# Emanuel_textured_walkway_V1.net
KiCad netlist of a schematic drawn in EAGLE
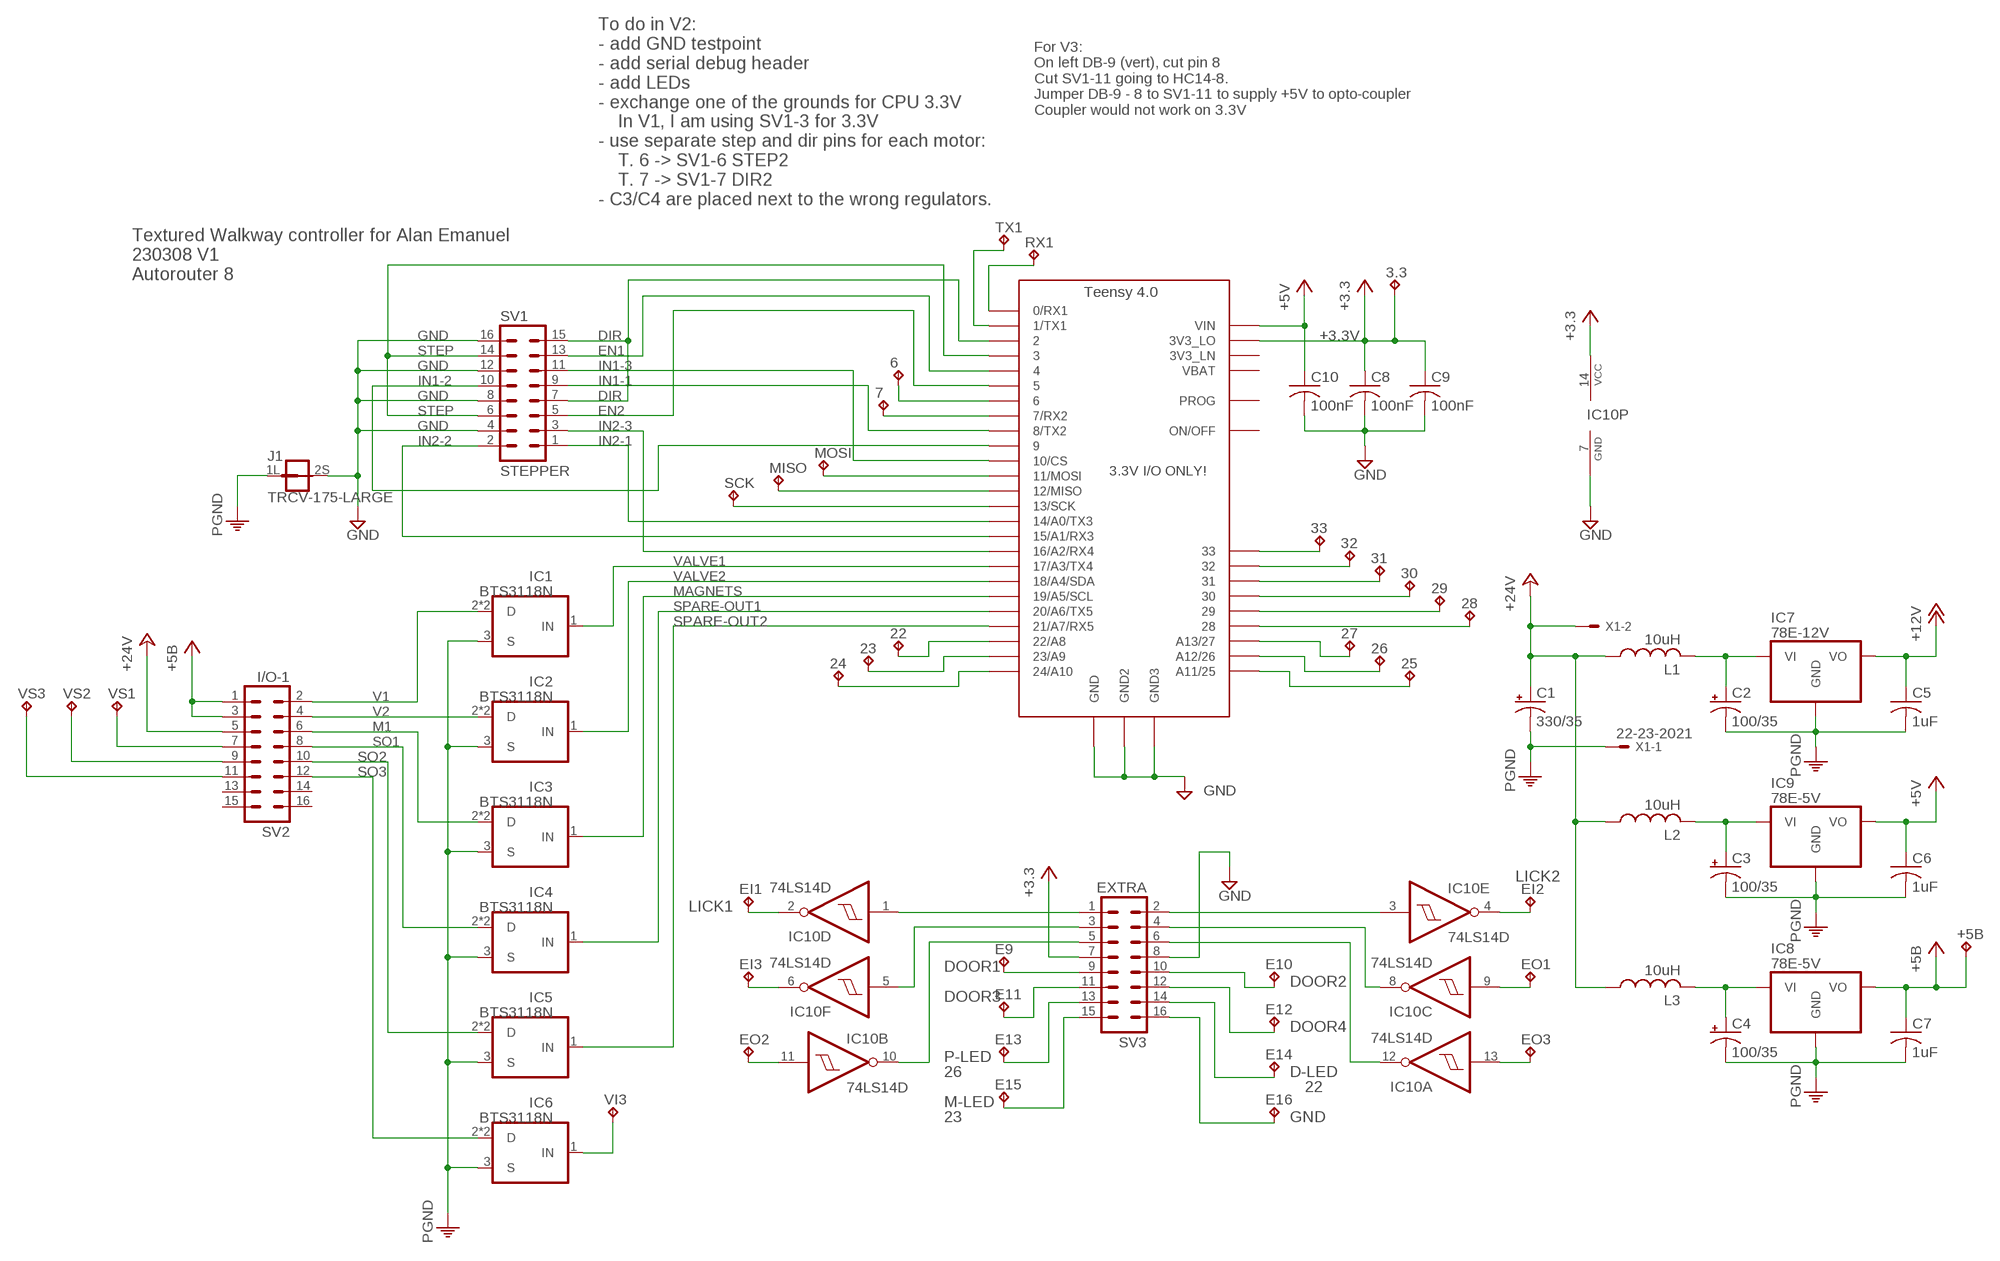
[diagram p0: schematic, sheet 1]

(export (version "E")
  (design (tool "Eeschema 10.0.6"))
  (components
    (comp (ref "+5B")
      (value "TP-040-100")
      (footprint "eagle-import:P1-040-100")
      (libsource (lib "eagle-import") (part "TP-040-100"))
    )
    (comp (ref "3.3")
      (value "3.3")
      (footprint "eagle-import:P1-040-100")
      (libsource (lib "eagle-import") (part "TP-040-100"))
    )
    (comp (ref "6")
      (value "TP-040-100")
      (footprint "eagle-import:P1-040-100")
      (libsource (lib "eagle-import") (part "TP-040-100"))
    )
    (comp (ref "7")
      (value "TP-040-100")
      (footprint "eagle-import:P1-040-100")
      (libsource (lib "eagle-import") (part "TP-040-100"))
    )
    (comp (ref "22")
      (value "TP-040-100")
      (footprint "eagle-import:P1-040-100")
      (libsource (lib "eagle-import") (part "TP-040-100"))
    )
    (comp (ref "23")
      (value "TP-040-100")
      (footprint "eagle-import:P1-040-100")
      (libsource (lib "eagle-import") (part "TP-040-100"))
    )
    (comp (ref "24")
      (value "TP-040-100")
      (footprint "eagle-import:P1-040-100")
      (libsource (lib "eagle-import") (part "TP-040-100"))
    )
    (comp (ref "25")
      (value "TP-040-100")
      (footprint "eagle-import:P1-040-100")
      (libsource (lib "eagle-import") (part "TP-040-100"))
    )
    (comp (ref "26")
      (value "TP-040-100")
      (footprint "eagle-import:P1-040-100")
      (libsource (lib "eagle-import") (part "TP-040-100"))
    )
    (comp (ref "27")
      (value "TP-040-100")
      (footprint "eagle-import:P1-040-100")
      (libsource (lib "eagle-import") (part "TP-040-100"))
    )
    (comp (ref "28")
      (value "TP-040-100")
      (footprint "eagle-import:P1-040-100")
      (libsource (lib "eagle-import") (part "TP-040-100"))
    )
    (comp (ref "29")
      (value "TP-040-100")
      (footprint "eagle-import:P1-040-100")
      (libsource (lib "eagle-import") (part "TP-040-100"))
    )
    (comp (ref "30")
      (value "TP-040-100")
      (footprint "eagle-import:P1-040-100")
      (libsource (lib "eagle-import") (part "TP-040-100"))
    )
    (comp (ref "31")
      (value "TP-040-100")
      (footprint "eagle-import:P1-040-100")
      (libsource (lib "eagle-import") (part "TP-040-100"))
    )
    (comp (ref "32")
      (value "TP-040-100")
      (footprint "eagle-import:P1-040-100")
      (libsource (lib "eagle-import") (part "TP-040-100"))
    )
    (comp (ref "33")
      (value "TP-040-100")
      (footprint "eagle-import:P1-040-100")
      (libsource (lib "eagle-import") (part "TP-040-100"))
    )
    (comp (ref "C1")
      (value "330/35")
      (footprint "eagle-import:140CLH-1010")
      (libsource (lib "eagle-import") (part "CPOL-US140CLH-1010"))
    )
    (comp (ref "C2")
      (value "100/35")
      (footprint "eagle-import:140CLH-0810")
      (libsource (lib "eagle-import") (part "CPOL-US140CLH-0810"))
    )
    (comp (ref "C3")
      (value "100/35")
      (footprint "eagle-import:140CLH-0810")
      (libsource (lib "eagle-import") (part "CPOL-US140CLH-0810"))
    )
    (comp (ref "C4")
      (value "100/35")
      (footprint "eagle-import:140CLH-0810")
      (libsource (lib "eagle-import") (part "CPOL-US140CLH-0810"))
    )
    (comp (ref "C5")
      (value "1uF")
      (footprint "eagle-import:C0805")
      (libsource (lib "eagle-import") (part "C-USC0805"))
    )
    (comp (ref "C6")
      (value "1uF")
      (footprint "eagle-import:C0805")
      (libsource (lib "eagle-import") (part "C-USC0805"))
    )
    (comp (ref "C7")
      (value "1uF")
      (footprint "eagle-import:C0805")
      (libsource (lib "eagle-import") (part "C-USC0805"))
    )
    (comp (ref "C8")
      (value "100nF")
      (footprint "eagle-import:C0805")
      (libsource (lib "eagle-import") (part "C-USC0805"))
    )
    (comp (ref "C9")
      (value "100nF")
      (footprint "eagle-import:C0805")
      (libsource (lib "eagle-import") (part "C-USC0805"))
    )
    (comp (ref "C10")
      (value "100nF")
      (footprint "eagle-import:C0805")
      (libsource (lib "eagle-import") (part "C-USC0805"))
    )
    (comp (ref "E9")
      (value "TP-040-100")
      (footprint "eagle-import:P1-040-100")
      (libsource (lib "eagle-import") (part "TP-040-100"))
    )
    (comp (ref "E10")
      (value "TP-040-100")
      (footprint "eagle-import:P1-040-100")
      (libsource (lib "eagle-import") (part "TP-040-100"))
    )
    (comp (ref "E11")
      (value "TP-040-100")
      (footprint "eagle-import:P1-040-100")
      (libsource (lib "eagle-import") (part "TP-040-100"))
    )
    (comp (ref "E12")
      (value "TP-040-100")
      (footprint "eagle-import:P1-040-100")
      (libsource (lib "eagle-import") (part "TP-040-100"))
    )
    (comp (ref "E13")
      (value "TP-040-100")
      (footprint "eagle-import:P1-040-100")
      (libsource (lib "eagle-import") (part "TP-040-100"))
    )
    (comp (ref "E14")
      (value "TP-040-100")
      (footprint "eagle-import:P1-040-100")
      (libsource (lib "eagle-import") (part "TP-040-100"))
    )
    (comp (ref "E15")
      (value "TP-040-100")
      (footprint "eagle-import:P1-040-100")
      (libsource (lib "eagle-import") (part "TP-040-100"))
    )
    (comp (ref "E16")
      (value "TP-040-100")
      (footprint "eagle-import:P1-040-100")
      (libsource (lib "eagle-import") (part "TP-040-100"))
    )
    (comp (ref "EI1")
      (value "TP-040-100")
      (footprint "eagle-import:P1-040-100")
      (libsource (lib "eagle-import") (part "TP-040-100"))
    )
    (comp (ref "EI2")
      (value "TP-040-100")
      (footprint "eagle-import:P1-040-100")
      (libsource (lib "eagle-import") (part "TP-040-100"))
    )
    (comp (ref "EI3")
      (value "TP-040-100")
      (footprint "eagle-import:P1-040-100")
      (libsource (lib "eagle-import") (part "TP-040-100"))
    )
    (comp (ref "EO1")
      (value "TP-040-100")
      (footprint "eagle-import:P1-040-100")
      (libsource (lib "eagle-import") (part "TP-040-100"))
    )
    (comp (ref "EO2")
      (value "TP-040-100")
      (footprint "eagle-import:P1-040-100")
      (libsource (lib "eagle-import") (part "TP-040-100"))
    )
    (comp (ref "EO3")
      (value "TP-040-100")
      (footprint "eagle-import:P1-040-100")
      (libsource (lib "eagle-import") (part "TP-040-100"))
    )
    (comp (ref "IC1")
      (value "BTS3118N")
      (footprint "eagle-import:SOT223")
      (libsource (lib "eagle-import") (part "BTS3118N"))
    )
    (comp (ref "IC2")
      (value "BTS3118N")
      (footprint "eagle-import:SOT223")
      (libsource (lib "eagle-import") (part "BTS3118N"))
    )
    (comp (ref "IC3")
      (value "BTS3118N")
      (footprint "eagle-import:SOT223")
      (libsource (lib "eagle-import") (part "BTS3118N"))
    )
    (comp (ref "IC4")
      (value "BTS3118N")
      (footprint "eagle-import:SOT223")
      (libsource (lib "eagle-import") (part "BTS3118N"))
    )
    (comp (ref "IC5")
      (value "BTS3118N")
      (footprint "eagle-import:SOT223")
      (libsource (lib "eagle-import") (part "BTS3118N"))
    )
    (comp (ref "IC6")
      (value "BTS3118N")
      (footprint "eagle-import:SOT223")
      (libsource (lib "eagle-import") (part "BTS3118N"))
    )
    (comp (ref "IC7")
      (value "78E-12V")
      (footprint "eagle-import:RECOM-R-78E")
      (libsource (lib "eagle-import") (part "RECOM-R-78E"))
    )
    (comp (ref "IC8")
      (value "78E-5V")
      (footprint "eagle-import:RECOM-R-78E")
      (libsource (lib "eagle-import") (part "RECOM-R-78E"))
    )
    (comp (ref "IC9")
      (value "78E-5V")
      (footprint "eagle-import:RECOM-R-78E")
      (libsource (lib "eagle-import") (part "RECOM-R-78E"))
    )
    (comp (ref "IC10")
      (value "74LS14D")
      (footprint "eagle-import:SO14")
      (libsource (lib "eagle-import") (part "7414DLS"))
    )
    (comp (ref "J1")
      (value "TRCV-175-LARGE")
      (footprint "eagle-import:JUMPER-TRACE-CONVERT-LARGER-PADS-175")
      (libsource (lib "eagle-import") (part "TRCV-175-LARGE"))
    )
    (comp (ref "L1")
      (value "10uH")
      (footprint "eagle-import:L1812")
      (libsource (lib "eagle-import") (part "L-USL1812"))
    )
    (comp (ref "L2")
      (value "10uH")
      (footprint "eagle-import:L1812")
      (libsource (lib "eagle-import") (part "L-USL1812"))
    )
    (comp (ref "L3")
      (value "10uH")
      (footprint "eagle-import:L1812")
      (libsource (lib "eagle-import") (part "L-USL1812"))
    )
    (comp (ref "MISO")
      (value "TP-040-100")
      (footprint "eagle-import:P1-040-100")
      (libsource (lib "eagle-import") (part "TP-040-100"))
    )
    (comp (ref "MOSI")
      (value "TP-040-100")
      (footprint "eagle-import:P1-040-100")
      (libsource (lib "eagle-import") (part "TP-040-100"))
    )
    (comp (ref "RX1")
      (value "TP-040-100")
      (footprint "eagle-import:P1-040-100")
      (libsource (lib "eagle-import") (part "TP-040-100"))
    )
    (comp (ref "SCK")
      (value "TP-040-100")
      (footprint "eagle-import:P1-040-100")
      (libsource (lib "eagle-import") (part "TP-040-100"))
    )
    (comp (ref "SV1")
      (value "STEPPER")
      (footprint "eagle-import:ML16")
      (libsource (lib "eagle-import") (part "ML16"))
    )
    (comp (ref "SV2")
      (value "I/O-1")
      (footprint "eagle-import:ML16")
      (libsource (lib "eagle-import") (part "ML16"))
    )
    (comp (ref "SV3")
      (value "EXTRA")
      (footprint "eagle-import:ML16")
      (libsource (lib "eagle-import") (part "ML16"))
    )
    (comp (ref "TX1")
      (value "TP-040-100")
      (footprint "eagle-import:P1-040-100")
      (libsource (lib "eagle-import") (part "TP-040-100"))
    )
    (comp (ref "U$1")
      (value "TEENSY_4.0_WITH_24-33")
      (footprint "eagle-import:TEENSY_4.0_WITH_24-33")
      (libsource (lib "eagle-import") (part "TEENSY_4.0_WITH_24-33"))
    )
    (comp (ref "VI3")
      (value "TP-040-100")
      (footprint "eagle-import:P1-040-100")
      (libsource (lib "eagle-import") (part "TP-040-100"))
    )
    (comp (ref "VS1")
      (value "TP-040-100")
      (footprint "eagle-import:P1-040-100")
      (libsource (lib "eagle-import") (part "TP-040-100"))
    )
    (comp (ref "VS2")
      (value "TP-040-100")
      (footprint "eagle-import:P1-040-100")
      (libsource (lib "eagle-import") (part "TP-040-100"))
    )
    (comp (ref "VS3")
      (value "TP-040-100")
      (footprint "eagle-import:P1-040-100")
      (libsource (lib "eagle-import") (part "TP-040-100"))
    )
    (comp (ref "X1")
      (value "22-23-2021")
      (footprint "eagle-import:22-23-2021")
      (fields (field (name "MF") "MOLEX"))
      (libsource (lib "eagle-import") (part "22-23-2021"))
    )
  )
  (nets
    (net (code "1") (name "+3.3") (class "Default")
      (node (ref "3.3") (pin "P$1") (pinfunction "TP_P$1") (pintype "passive"))
      (node (ref "C8") (pin "1") (pinfunction "1_1") (pintype "passive"))
      (node (ref "C9") (pin "1") (pinfunction "1_1") (pintype "passive"))
      (node (ref "IC10") (pin "14") (pinfunction "VCC_14") (pintype "power_in"))
      (node (ref "SV3") (pin "7") (pinfunction "7_7") (pintype "passive"))
      (node (ref "U$1") (pin "3V3_LO") (pinfunction "3V3_LO_3V3_LO") (pintype "bidirectional"))
    )
    (net (code "2") (name "+5B") (class "Default")
      (node (ref "+5B") (pin "P$1") (pinfunction "TP_P$1") (pintype "passive"))
      (node (ref "C7") (pin "1") (pinfunction "1_1") (pintype "passive"))
      (node (ref "IC8") (pin "3") (pinfunction "VO_3") (pintype "passive"))
      (node (ref "SV2") (pin "1") (pinfunction "1_1") (pintype "passive"))
      (node (ref "SV2") (pin "3") (pinfunction "3_3") (pintype "passive"))
    )
    (net (code "3") (name "+5V") (class "Default")
      (node (ref "C10") (pin "1") (pinfunction "1_1") (pintype "passive"))
      (node (ref "C6") (pin "1") (pinfunction "1_1") (pintype "passive"))
      (node (ref "IC9") (pin "3") (pinfunction "VO_3") (pintype "passive"))
      (node (ref "U$1") (pin "VIN") (pinfunction "VIN_VIN") (pintype "bidirectional"))
    )
    (net (code "4") (name "+12V") (class "Default")
      (node (ref "C5") (pin "1") (pinfunction "1_1") (pintype "passive"))
      (node (ref "IC7") (pin "3") (pinfunction "VO_3") (pintype "passive"))
    )
    (net (code "5") (name "+24V") (class "Default")
      (node (ref "C1") (pin "+") (pinfunction "+_+") (pintype "passive"))
      (node (ref "L1") (pin "1") (pinfunction "1_1") (pintype "passive"))
      (node (ref "L2") (pin "1") (pinfunction "1_1") (pintype "passive"))
      (node (ref "L3") (pin "1") (pinfunction "1_1") (pintype "passive"))
      (node (ref "SV2") (pin "5") (pinfunction "5_5") (pintype "passive"))
      (node (ref "X1") (pin "2") (pinfunction "S_2") (pintype "passive"))
    )
    (net (code "6") (name "/DIR") (class "Default")
      (node (ref "SV1") (pin "15") (pinfunction "15_15") (pintype "passive"))
      (node (ref "SV1") (pin "7") (pinfunction "7_7") (pintype "passive"))
      (node (ref "U$1") (pin "2") (pinfunction "2_2") (pintype "bidirectional"))
    )
    (net (code "7") (name "/EN1") (class "Default")
      (node (ref "SV1") (pin "13") (pinfunction "13_13") (pintype "passive"))
      (node (ref "U$1") (pin "4") (pinfunction "4_4") (pintype "bidirectional"))
    )
    (net (code "8") (name "/EN2") (class "Default")
      (node (ref "SV1") (pin "5") (pinfunction "5_5") (pintype "passive"))
      (node (ref "U$1") (pin "5") (pinfunction "5_5") (pintype "bidirectional"))
    )
    (net (code "9") (name "/IN1-1") (class "Default")
      (node (ref "SV1") (pin "9") (pinfunction "9_9") (pintype "passive"))
      (node (ref "U$1") (pin "8") (pinfunction "8/TX2_8") (pintype "bidirectional"))
    )
    (net (code "10") (name "/IN1-2") (class "Default")
      (node (ref "SV1") (pin "10") (pinfunction "10_10") (pintype "passive"))
      (node (ref "U$1") (pin "9") (pinfunction "9_9") (pintype "bidirectional"))
    )
    (net (code "11") (name "/IN1-3") (class "Default")
      (node (ref "SV1") (pin "11") (pinfunction "11_11") (pintype "passive"))
      (node (ref "U$1") (pin "10/CS") (pinfunction "10/CS_10/CS") (pintype "bidirectional"))
    )
    (net (code "12") (name "/IN2-1") (class "Default")
      (node (ref "SV1") (pin "1") (pinfunction "1_1") (pintype "passive"))
      (node (ref "U$1") (pin "14/A0") (pinfunction "14/A0/TX3_14/A0") (pintype "bidirectional"))
    )
    (net (code "13") (name "/IN2-2") (class "Default")
      (node (ref "SV1") (pin "2") (pinfunction "2_2") (pintype "passive"))
      (node (ref "U$1") (pin "15/A1") (pinfunction "15/A1/RX3_15/A1") (pintype "bidirectional"))
    )
    (net (code "14") (name "/IN2-3") (class "Default")
      (node (ref "SV1") (pin "3") (pinfunction "3_3") (pintype "passive"))
      (node (ref "U$1") (pin "16/A2") (pinfunction "16/A2/RX4_16/A2") (pintype "bidirectional"))
    )
    (net (code "15") (name "/M1") (class "Default")
      (node (ref "IC3") (pin "2") (pinfunction "D_2") (pintype "passive"))
      (node (ref "IC3") (pin "4") (pinfunction "D_4") (pintype "passive"))
      (node (ref "SV2") (pin "6") (pinfunction "6_6") (pintype "passive"))
    )
    (net (code "16") (name "/MAGNETS") (class "Default")
      (node (ref "IC3") (pin "1") (pinfunction "IN_1") (pintype "input"))
      (node (ref "U$1") (pin "19/A5/SCL") (pinfunction "19/A5/SCL_19/A5/SCL") (pintype "bidirectional"))
    )
    (net (code "17") (name "/SO1") (class "Default")
      (node (ref "IC4") (pin "2") (pinfunction "D_2") (pintype "passive"))
      (node (ref "IC4") (pin "4") (pinfunction "D_4") (pintype "passive"))
      (node (ref "SV2") (pin "8") (pinfunction "8_8") (pintype "passive"))
    )
    (net (code "18") (name "/SO2") (class "Default")
      (node (ref "IC5") (pin "2") (pinfunction "D_2") (pintype "passive"))
      (node (ref "IC5") (pin "4") (pinfunction "D_4") (pintype "passive"))
      (node (ref "SV2") (pin "10") (pinfunction "10_10") (pintype "passive"))
    )
    (net (code "19") (name "/SO3") (class "Default")
      (node (ref "IC6") (pin "2") (pinfunction "D_2") (pintype "passive"))
      (node (ref "IC6") (pin "4") (pinfunction "D_4") (pintype "passive"))
      (node (ref "SV2") (pin "12") (pinfunction "12_12") (pintype "passive"))
    )
    (net (code "20") (name "/SPARE-OUT1") (class "Default")
      (node (ref "IC4") (pin "1") (pinfunction "IN_1") (pintype "input"))
      (node (ref "U$1") (pin "20/A6") (pinfunction "20/A6/TX5_20/A6") (pintype "bidirectional"))
    )
    (net (code "21") (name "/SPARE-OUT2") (class "Default")
      (node (ref "IC5") (pin "1") (pinfunction "IN_1") (pintype "input"))
      (node (ref "U$1") (pin "21/A7") (pinfunction "21/A7/RX5_21/A7") (pintype "bidirectional"))
    )
    (net (code "22") (name "/STEP") (class "Default")
      (node (ref "SV1") (pin "14") (pinfunction "14_14") (pintype "passive"))
      (node (ref "SV1") (pin "6") (pinfunction "6_6") (pintype "passive"))
      (node (ref "U$1") (pin "3") (pinfunction "3_3") (pintype "bidirectional"))
    )
    (net (code "23") (name "/V1") (class "Default")
      (node (ref "IC1") (pin "2") (pinfunction "D_2") (pintype "passive"))
      (node (ref "IC1") (pin "4") (pinfunction "D_4") (pintype "passive"))
      (node (ref "SV2") (pin "2") (pinfunction "2_2") (pintype "passive"))
    )
    (net (code "24") (name "/V2") (class "Default")
      (node (ref "IC2") (pin "2") (pinfunction "D_2") (pintype "passive"))
      (node (ref "IC2") (pin "4") (pinfunction "D_4") (pintype "passive"))
      (node (ref "SV2") (pin "4") (pinfunction "4_4") (pintype "passive"))
    )
    (net (code "25") (name "/VALVE1") (class "Default")
      (node (ref "IC1") (pin "1") (pinfunction "IN_1") (pintype "input"))
      (node (ref "U$1") (pin "17/A3") (pinfunction "17/A3/TX4_17/A3") (pintype "bidirectional"))
    )
    (net (code "26") (name "/VALVE2") (class "Default")
      (node (ref "IC2") (pin "1") (pinfunction "IN_1") (pintype "input"))
      (node (ref "U$1") (pin "18/A4/SDA") (pinfunction "18/A4/SDA_18/A4/SDA") (pintype "bidirectional"))
    )
    (net (code "27") (name "GND") (class "Default")
      (node (ref "C10") (pin "2") (pinfunction "2_2") (pintype "passive"))
      (node (ref "C8") (pin "2") (pinfunction "2_2") (pintype "passive"))
      (node (ref "C9") (pin "2") (pinfunction "2_2") (pintype "passive"))
      (node (ref "IC10") (pin "7") (pinfunction "GND_7") (pintype "power_in"))
      (node (ref "J1") (pin "2S") (pinfunction "2_2S") (pintype "passive"))
      (node (ref "SV1") (pin "12") (pinfunction "12_12") (pintype "passive"))
      (node (ref "SV1") (pin "16") (pinfunction "16_16") (pintype "passive"))
      (node (ref "SV1") (pin "4") (pinfunction "4_4") (pintype "passive"))
      (node (ref "SV1") (pin "8") (pinfunction "8_8") (pintype "passive"))
      (node (ref "SV3") (pin "8") (pinfunction "8_8") (pintype "passive"))
      (node (ref "U$1") (pin "GND") (pinfunction "GND_GND") (pintype "bidirectional"))
      (node (ref "U$1") (pin "GND2") (pinfunction "GND2_GND2") (pintype "bidirectional"))
      (node (ref "U$1") (pin "GND3") (pinfunction "GND3_GND3") (pintype "bidirectional"))
    )
    (net (code "28") (name "Net-(6-TP)") (class "Default")
      (node (ref "6") (pin "P$1") (pinfunction "TP_P$1") (pintype "passive"))
      (node (ref "U$1") (pin "6") (pinfunction "6_6") (pintype "bidirectional"))
    )
    (net (code "29") (name "Net-(7-TP)") (class "Default")
      (node (ref "7") (pin "P$1") (pinfunction "TP_P$1") (pintype "passive"))
      (node (ref "U$1") (pin "7") (pinfunction "7/RX2_7") (pintype "bidirectional"))
    )
    (net (code "30") (name "Net-(22-TP)") (class "Default")
      (node (ref "22") (pin "P$1") (pinfunction "TP_P$1") (pintype "passive"))
      (node (ref "U$1") (pin "22/A8") (pinfunction "22/A8_22/A8") (pintype "bidirectional"))
    )
    (net (code "31") (name "Net-(23-TP)") (class "Default")
      (node (ref "23") (pin "P$1") (pinfunction "TP_P$1") (pintype "passive"))
      (node (ref "U$1") (pin "23/A9") (pinfunction "23/A9_23/A9") (pintype "bidirectional"))
    )
    (net (code "32") (name "Net-(24-TP)") (class "Default")
      (node (ref "24") (pin "P$1") (pinfunction "TP_P$1") (pintype "passive"))
      (node (ref "U$1") (pin "24") (pinfunction "24/A10_24") (pintype "bidirectional"))
    )
    (net (code "33") (name "Net-(25-TP)") (class "Default")
      (node (ref "25") (pin "P$1") (pinfunction "TP_P$1") (pintype "passive"))
      (node (ref "U$1") (pin "25") (pinfunction "A11/25_25") (pintype "bidirectional"))
    )
    (net (code "34") (name "Net-(26-TP)") (class "Default")
      (node (ref "26") (pin "P$1") (pinfunction "TP_P$1") (pintype "passive"))
      (node (ref "U$1") (pin "26") (pinfunction "A12/26_26") (pintype "bidirectional"))
    )
    (net (code "35") (name "Net-(27-TP)") (class "Default")
      (node (ref "27") (pin "P$1") (pinfunction "TP_P$1") (pintype "passive"))
      (node (ref "U$1") (pin "27") (pinfunction "A13/27_27") (pintype "bidirectional"))
    )
    (net (code "36") (name "Net-(28-TP)") (class "Default")
      (node (ref "28") (pin "P$1") (pinfunction "TP_P$1") (pintype "passive"))
      (node (ref "U$1") (pin "28") (pinfunction "28_28") (pintype "bidirectional"))
    )
    (net (code "37") (name "Net-(29-TP)") (class "Default")
      (node (ref "29") (pin "P$1") (pinfunction "TP_P$1") (pintype "passive"))
      (node (ref "U$1") (pin "29") (pinfunction "29_29") (pintype "bidirectional"))
    )
    (net (code "38") (name "Net-(30-TP)") (class "Default")
      (node (ref "30") (pin "P$1") (pinfunction "TP_P$1") (pintype "passive"))
      (node (ref "U$1") (pin "30") (pinfunction "30_30") (pintype "bidirectional"))
    )
    (net (code "39") (name "Net-(31-TP)") (class "Default")
      (node (ref "31") (pin "P$1") (pinfunction "TP_P$1") (pintype "passive"))
      (node (ref "U$1") (pin "31") (pinfunction "31_31") (pintype "bidirectional"))
    )
    (net (code "40") (name "Net-(32-TP)") (class "Default")
      (node (ref "32") (pin "P$1") (pinfunction "TP_P$1") (pintype "passive"))
      (node (ref "U$1") (pin "32") (pinfunction "32_32") (pintype "bidirectional"))
    )
    (net (code "41") (name "Net-(33-TP)") (class "Default")
      (node (ref "33") (pin "P$1") (pinfunction "TP_P$1") (pintype "passive"))
      (node (ref "U$1") (pin "33") (pinfunction "33_33") (pintype "bidirectional"))
    )
    (net (code "42") (name "Net-(E9-TP)") (class "Default")
      (node (ref "E9") (pin "P$1") (pinfunction "TP_P$1") (pintype "passive"))
      (node (ref "SV3") (pin "9") (pinfunction "9_9") (pintype "passive"))
    )
    (net (code "43") (name "Net-(E10-TP)") (class "Default")
      (node (ref "E10") (pin "P$1") (pinfunction "TP_P$1") (pintype "passive"))
      (node (ref "SV3") (pin "10") (pinfunction "10_10") (pintype "passive"))
    )
    (net (code "44") (name "Net-(E11-TP)") (class "Default")
      (node (ref "E11") (pin "P$1") (pinfunction "TP_P$1") (pintype "passive"))
      (node (ref "SV3") (pin "11") (pinfunction "11_11") (pintype "passive"))
    )
    (net (code "45") (name "Net-(E12-TP)") (class "Default")
      (node (ref "E12") (pin "P$1") (pinfunction "TP_P$1") (pintype "passive"))
      (node (ref "SV3") (pin "12") (pinfunction "12_12") (pintype "passive"))
    )
    (net (code "46") (name "Net-(E13-TP)") (class "Default")
      (node (ref "E13") (pin "P$1") (pinfunction "TP_P$1") (pintype "passive"))
      (node (ref "SV3") (pin "13") (pinfunction "13_13") (pintype "passive"))
    )
    (net (code "47") (name "Net-(E14-TP)") (class "Default")
      (node (ref "E14") (pin "P$1") (pinfunction "TP_P$1") (pintype "passive"))
      (node (ref "SV3") (pin "14") (pinfunction "14_14") (pintype "passive"))
    )
    (net (code "48") (name "Net-(E15-TP)") (class "Default")
      (node (ref "E15") (pin "P$1") (pinfunction "TP_P$1") (pintype "passive"))
      (node (ref "SV3") (pin "15") (pinfunction "15_15") (pintype "passive"))
    )
    (net (code "49") (name "Net-(E16-TP)") (class "Default")
      (node (ref "E16") (pin "P$1") (pinfunction "TP_P$1") (pintype "passive"))
      (node (ref "SV3") (pin "16") (pinfunction "16_16") (pintype "passive"))
    )
    (net (code "50") (name "Net-(EI1-TP)") (class "Default")
      (node (ref "EI1") (pin "P$1") (pinfunction "TP_P$1") (pintype "passive"))
      (node (ref "IC10") (pin "2") (pinfunction "O_2") (pintype "output"))
    )
    (net (code "51") (name "Net-(EI2-TP)") (class "Default")
      (node (ref "EI2") (pin "P$1") (pinfunction "TP_P$1") (pintype "passive"))
      (node (ref "IC10") (pin "4") (pinfunction "O_4") (pintype "output"))
    )
    (net (code "52") (name "Net-(EI3-TP)") (class "Default")
      (node (ref "EI3") (pin "P$1") (pinfunction "TP_P$1") (pintype "passive"))
      (node (ref "IC10") (pin "6") (pinfunction "O_6") (pintype "output"))
    )
    (net (code "53") (name "Net-(EO1-TP)") (class "Default")
      (node (ref "EO1") (pin "P$1") (pinfunction "TP_P$1") (pintype "passive"))
      (node (ref "IC10") (pin "9") (pinfunction "I_9") (pintype "input"))
    )
    (net (code "54") (name "Net-(EO2-TP)") (class "Default")
      (node (ref "EO2") (pin "P$1") (pinfunction "TP_P$1") (pintype "passive"))
      (node (ref "IC10") (pin "11") (pinfunction "I_11") (pintype "input"))
    )
    (net (code "55") (name "Net-(EO3-TP)") (class "Default")
      (node (ref "EO3") (pin "P$1") (pinfunction "TP_P$1") (pintype "passive"))
      (node (ref "IC10") (pin "13") (pinfunction "I_13") (pintype "input"))
    )
    (net (code "56") (name "Net-(IC6-IN)") (class "Default")
      (node (ref "IC6") (pin "1") (pinfunction "IN_1") (pintype "input"))
      (node (ref "VI3") (pin "P$1") (pinfunction "TP_P$1") (pintype "passive"))
    )
    (net (code "57") (name "Net-(IC7-VI)") (class "Default")
      (node (ref "C2") (pin "+") (pinfunction "+_+") (pintype "passive"))
      (node (ref "IC7") (pin "1") (pinfunction "VI_1") (pintype "input"))
      (node (ref "L1") (pin "2") (pinfunction "2_2") (pintype "passive"))
    )
    (net (code "58") (name "Net-(IC8-VI)") (class "Default")
      (node (ref "C4") (pin "+") (pinfunction "+_+") (pintype "passive"))
      (node (ref "IC8") (pin "1") (pinfunction "VI_1") (pintype "input"))
      (node (ref "L3") (pin "2") (pinfunction "2_2") (pintype "passive"))
    )
    (net (code "59") (name "Net-(IC9-VI)") (class "Default")
      (node (ref "C3") (pin "+") (pinfunction "+_+") (pintype "passive"))
      (node (ref "IC9") (pin "1") (pinfunction "VI_1") (pintype "input"))
      (node (ref "L2") (pin "2") (pinfunction "2_2") (pintype "passive"))
    )
    (net (code "60") (name "Net-(IC10A-O)") (class "Default")
      (node (ref "IC10") (pin "12") (pinfunction "O_12") (pintype "output"))
      (node (ref "SV3") (pin "6") (pinfunction "6_6") (pintype "passive"))
    )
    (net (code "61") (name "Net-(IC10B-O)") (class "Default")
      (node (ref "IC10") (pin "10") (pinfunction "O_10") (pintype "output"))
      (node (ref "SV3") (pin "5") (pinfunction "5_5") (pintype "passive"))
    )
    (net (code "62") (name "Net-(IC10C-O)") (class "Default")
      (node (ref "IC10") (pin "8") (pinfunction "O_8") (pintype "output"))
      (node (ref "SV3") (pin "4") (pinfunction "4_4") (pintype "passive"))
    )
    (net (code "63") (name "Net-(IC10D-I)") (class "Default")
      (node (ref "IC10") (pin "1") (pinfunction "I_1") (pintype "input"))
      (node (ref "SV3") (pin "1") (pinfunction "1_1") (pintype "passive"))
    )
    (net (code "64") (name "Net-(IC10E-I)") (class "Default")
      (node (ref "IC10") (pin "3") (pinfunction "I_3") (pintype "input"))
      (node (ref "SV3") (pin "2") (pinfunction "2_2") (pintype "passive"))
    )
    (net (code "65") (name "Net-(IC10F-I)") (class "Default")
      (node (ref "IC10") (pin "5") (pinfunction "I_5") (pintype "input"))
      (node (ref "SV3") (pin "3") (pinfunction "3_3") (pintype "passive"))
    )
    (net (code "66") (name "Net-(MISO-TP)") (class "Default")
      (node (ref "MISO") (pin "P$1") (pinfunction "TP_P$1") (pintype "passive"))
      (node (ref "U$1") (pin "12/MISO") (pinfunction "12/MISO_12/MISO") (pintype "bidirectional"))
    )
    (net (code "67") (name "Net-(MOSI-TP)") (class "Default")
      (node (ref "MOSI") (pin "P$1") (pinfunction "TP_P$1") (pintype "passive"))
      (node (ref "U$1") (pin "11/MOSI") (pinfunction "11/MOSI_11/MOSI") (pintype "bidirectional"))
    )
    (net (code "68") (name "Net-(RX1-TP)") (class "Default")
      (node (ref "RX1") (pin "P$1") (pinfunction "TP_P$1") (pintype "passive"))
      (node (ref "U$1") (pin "0/RX") (pinfunction "0/RX1_0/RX") (pintype "bidirectional"))
    )
    (net (code "69") (name "Net-(SCK-TP)") (class "Default")
      (node (ref "SCK") (pin "P$1") (pinfunction "TP_P$1") (pintype "passive"))
      (node (ref "U$1") (pin "13/SCK") (pinfunction "13/SCK_13/SCK") (pintype "bidirectional"))
    )
    (net (code "70") (name "Net-(TX1-TP)") (class "Default")
      (node (ref "TX1") (pin "P$1") (pinfunction "TP_P$1") (pintype "passive"))
      (node (ref "U$1") (pin "1/TX") (pinfunction "1/TX1_1/TX") (pintype "bidirectional"))
    )
    (net (code "71") (name "Net-(VS1-TP)") (class "Default")
      (node (ref "SV2") (pin "7") (pinfunction "7_7") (pintype "passive"))
      (node (ref "VS1") (pin "P$1") (pinfunction "TP_P$1") (pintype "passive"))
    )
    (net (code "72") (name "Net-(VS2-TP)") (class "Default")
      (node (ref "SV2") (pin "9") (pinfunction "9_9") (pintype "passive"))
      (node (ref "VS2") (pin "P$1") (pinfunction "TP_P$1") (pintype "passive"))
    )
    (net (code "73") (name "Net-(VS3-TP)") (class "Default")
      (node (ref "SV2") (pin "11") (pinfunction "11_11") (pintype "passive"))
      (node (ref "VS3") (pin "P$1") (pinfunction "TP_P$1") (pintype "passive"))
    )
    (net (code "74") (name "PGND") (class "Default")
      (node (ref "C1") (pin "-") (pinfunction "-_-") (pintype "passive"))
      (node (ref "C2") (pin "-") (pinfunction "-_-") (pintype "passive"))
      (node (ref "C3") (pin "-") (pinfunction "-_-") (pintype "passive"))
      (node (ref "C4") (pin "-") (pinfunction "-_-") (pintype "passive"))
      (node (ref "C5") (pin "2") (pinfunction "2_2") (pintype "passive"))
      (node (ref "C6") (pin "2") (pinfunction "2_2") (pintype "passive"))
      (node (ref "C7") (pin "2") (pinfunction "2_2") (pintype "passive"))
      (node (ref "IC1") (pin "3") (pinfunction "S_3") (pintype "passive"))
      (node (ref "IC2") (pin "3") (pinfunction "S_3") (pintype "passive"))
      (node (ref "IC3") (pin "3") (pinfunction "S_3") (pintype "passive"))
      (node (ref "IC4") (pin "3") (pinfunction "S_3") (pintype "passive"))
      (node (ref "IC5") (pin "3") (pinfunction "S_3") (pintype "passive"))
      (node (ref "IC6") (pin "3") (pinfunction "S_3") (pintype "passive"))
      (node (ref "IC7") (pin "2") (pinfunction "GND_2") (pintype "input"))
      (node (ref "IC8") (pin "2") (pinfunction "GND_2") (pintype "input"))
      (node (ref "IC9") (pin "2") (pinfunction "GND_2") (pintype "input"))
      (node (ref "J1") (pin "1L") (pinfunction "1_1L") (pintype "passive"))
      (node (ref "X1") (pin "1") (pinfunction "S_1") (pintype "passive"))
    )
    (net (code "75") (name "unconnected-(SV2-Pad13)") (class "Default")
      (node (ref "SV2") (pin "13") (pinfunction "13_13") (pintype "passive"))
    )
    (net (code "76") (name "unconnected-(SV2-Pad14)") (class "Default")
      (node (ref "SV2") (pin "14") (pinfunction "14_14") (pintype "passive"))
    )
    (net (code "77") (name "unconnected-(SV2-Pad15)") (class "Default")
      (node (ref "SV2") (pin "15") (pinfunction "15_15") (pintype "passive"))
    )
    (net (code "78") (name "unconnected-(SV2-Pad16)") (class "Default")
      (node (ref "SV2") (pin "16") (pinfunction "16_16") (pintype "passive"))
    )
    (net (code "79") (name "unconnected-(U$1-Pad3V3_LN)") (class "Default")
      (node (ref "U$1") (pin "3V3_LN") (pinfunction "3V3_LN_3V3_LN") (pintype "bidirectional"))
    )
    (net (code "80") (name "unconnected-(U$1-PadON{slash}OFF)") (class "Default")
      (node (ref "U$1") (pin "ON/OFF") (pinfunction "ON/OFF_ON/OFF") (pintype "bidirectional"))
    )
    (net (code "81") (name "unconnected-(U$1-PadPROG)") (class "Default")
      (node (ref "U$1") (pin "PROG") (pinfunction "PROG_PROG") (pintype "bidirectional"))
    )
    (net (code "82") (name "unconnected-(U$1-VBAT-PadVBAT\\)") (class "Default")
      (node (ref "U$1") (pin "VBAT\\") (pinfunction "VBAT_VBAT\\") (pintype "bidirectional"))
    )
  )
)
